# 08_-_CONNECTORS.net
KiCad netlist of a schematic drawn in Altium Designer
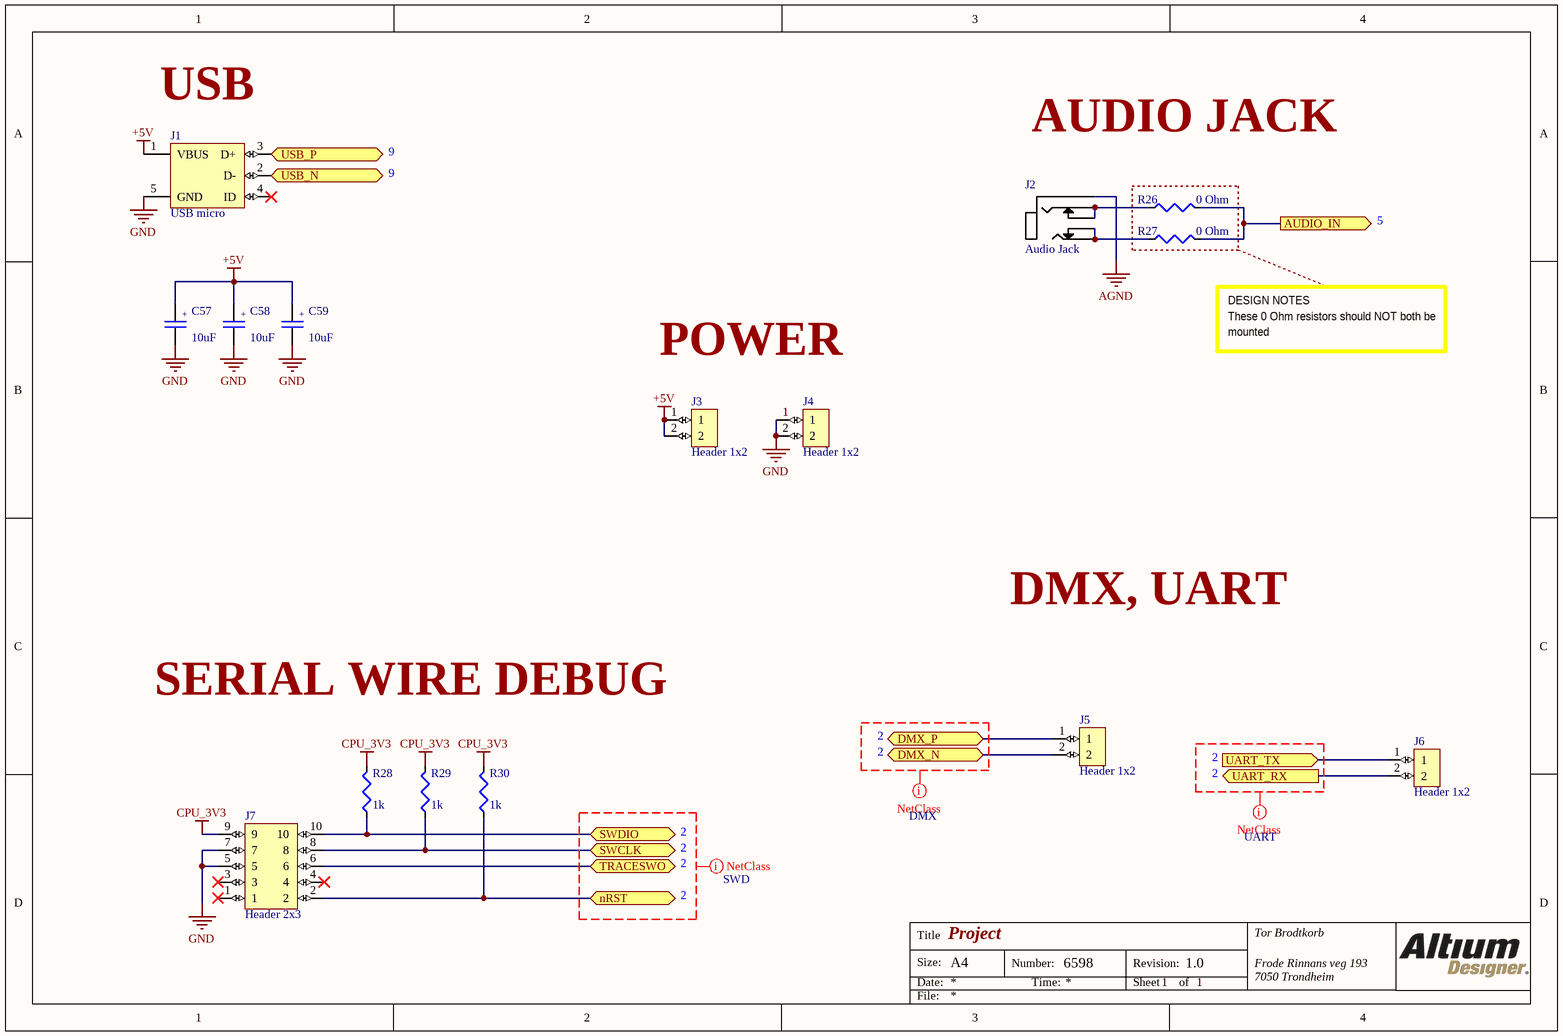
[diagram p0: [08] - CONNECTORS.SchDoc]

(export (version "E")
  (design (tool "Eeschema 10.0.6"))
  (components
    (comp (ref "C57")
      (value "10uF")
      (footprint "Capacitor electrolytic SMD 4x5.4")
      (description "El. Capacitor SMD 4x5.4")
      (fields (field (name "Comment") "EEE1HA2R2SR"))
      (libsource (lib "Passive components") (part "EEE1HA2R2SR"))
    )
    (comp (ref "C58")
      (value "10uF")
      (footprint "Capacitor electrolytic SMD 4x5.4")
      (description "El. Capacitor SMD 4x5.4")
      (fields (field (name "Comment") "EEE1HA2R2SR"))
      (libsource (lib "Passive components") (part "EEE1HA2R2SR"))
    )
    (comp (ref "C59")
      (value "10uF")
      (footprint "Capacitor electrolytic SMD 4x5.4")
      (description "El. Capacitor SMD 4x5.4")
      (fields (field (name "Comment") "EEE1HA2R2SR"))
      (libsource (lib "Passive components") (part "EEE1HA2R2SR"))
    )
    (comp (ref "J1")
      (value "USB micro")
      (footprint "USB micro")
      (libsource (lib "Connectors") (part "47590-0001"))
    )
    (comp (ref "J2")
      (value "Audio Jack")
      (footprint "Audio jack flat")
      (description "Audio jack flat 5 contacts")
      (libsource (lib "Connectors") (part "FC68133"))
    )
    (comp (ref "J3")
      (value "Header 1x2")
      (footprint "Header 1x2 2.54mm")
      (description "Header 1x2 2.54mm male")
      (libsource (lib "Connectors") (part "M20-9990246"))
    )
    (comp (ref "J4")
      (value "Header 1x2")
      (footprint "Header 1x2 2.54mm")
      (description "Header 1x2 2.54mm male")
      (libsource (lib "Connectors") (part "M20-9990246"))
    )
    (comp (ref "J5")
      (value "Header 1x2")
      (footprint "Header 1x2 2.54mm")
      (description "Header 1x2 2.54mm male")
      (libsource (lib "Connectors") (part "M20-9990246"))
    )
    (comp (ref "J6")
      (value "Header 1x2")
      (footprint "Header 1x2 2.54mm")
      (description "Header 1x2 2.54mm male")
      (libsource (lib "Connectors") (part "M20-9990246"))
    )
    (comp (ref "J7")
      (value "Header 2x3")
      (footprint "Header 2x5 1.27mm")
      (description "Header  2x5 1.27mm male")
      (libsource (lib "Connectors") (part "20021111-00010T4LF"))
    )
    (comp (ref "R26")
      (value "0 Ohm")
      (footprint "R0603")
      (description "R0603")
      (fields (field (name "Comment") "CPF-A-0603B100KE1"))
      (libsource (lib "Passive components") (part "CPF-A-0603B100KE1"))
    )
    (comp (ref "R27")
      (value "0 Ohm")
      (footprint "R0603")
      (description "R0603")
      (fields (field (name "Comment") "CPF-A-0603B100KE1"))
      (libsource (lib "Passive components") (part "CPF-A-0603B100KE1"))
    )
    (comp (ref "R28")
      (value "1k")
      (footprint "R0603")
      (description "R0603")
      (fields (field (name "Comment") "CPF-A-0603B100KE1"))
      (libsource (lib "Passive components") (part "CPF-A-0603B100KE1"))
    )
    (comp (ref "R29")
      (value "1k")
      (footprint "R0603")
      (description "R0603")
      (fields (field (name "Comment") "CPF-A-0603B100KE1"))
      (libsource (lib "Passive components") (part "CPF-A-0603B100KE1"))
    )
    (comp (ref "R30")
      (value "1k")
      (footprint "R0603")
      (description "R0603")
      (fields (field (name "Comment") "CPF-A-0603B100KE1"))
      (libsource (lib "Passive components") (part "CPF-A-0603B100KE1"))
    )
  )
  (nets
    (net (code "1") (name "+5V") (class "Default")
      (node (ref "C57") (pin "1") (pinfunction "1_1") (pintype "passive"))
      (node (ref "C58") (pin "1") (pinfunction "1_1") (pintype "passive"))
      (node (ref "C59") (pin "1") (pinfunction "1_1") (pintype "passive"))
      (node (ref "J1") (pin "1") (pinfunction "VBUS_1") (pintype "passive"))
      (node (ref "J3") (pin "1") (pinfunction "1_1") (pintype "bidirectional"))
      (node (ref "J3") (pin "2") (pinfunction "2_2") (pintype "bidirectional"))
    )
    (net (code "2") (name "/AUDIO_IN") (class "Default")
      (node (ref "R26") (pin "2") (pinfunction "2_2") (pintype "passive"))
      (node (ref "R27") (pin "2") (pinfunction "2_2") (pintype "passive"))
    )
    (net (code "3") (name "/DMX_N") (class "Default")
      (node (ref "J5") (pin "2") (pinfunction "2_2") (pintype "bidirectional"))
    )
    (net (code "4") (name "/DMX_P") (class "Default")
      (node (ref "J5") (pin "1") (pinfunction "1_1") (pintype "bidirectional"))
    )
    (net (code "5") (name "/SWCLK") (class "Default")
      (node (ref "J7") (pin "8") (pinfunction "8_8") (pintype "bidirectional"))
      (node (ref "R29") (pin "1") (pinfunction "1_1") (pintype "passive"))
    )
    (net (code "6") (name "/SWDIO") (class "Default")
      (node (ref "J7") (pin "10") (pinfunction "10_10") (pintype "bidirectional"))
      (node (ref "R28") (pin "1") (pinfunction "1_1") (pintype "passive"))
    )
    (net (code "7") (name "/TRACESWO") (class "Default")
      (node (ref "J7") (pin "6") (pinfunction "6_6") (pintype "bidirectional"))
    )
    (net (code "8") (name "/UART_RX") (class "Default")
      (node (ref "J6") (pin "2") (pinfunction "2_2") (pintype "bidirectional"))
    )
    (net (code "9") (name "/UART_TX") (class "Default")
      (node (ref "J6") (pin "1") (pinfunction "1_1") (pintype "bidirectional"))
    )
    (net (code "10") (name "/USB_N") (class "Default")
      (node (ref "J1") (pin "2") (pinfunction "D-_2") (pintype "bidirectional"))
    )
    (net (code "11") (name "/USB_P") (class "Default")
      (node (ref "J1") (pin "3") (pinfunction "D+_3") (pintype "bidirectional"))
    )
    (net (code "12") (name "/nRST") (class "Default")
      (node (ref "J7") (pin "2") (pinfunction "2_2") (pintype "bidirectional"))
      (node (ref "R30") (pin "1") (pinfunction "1_1") (pintype "passive"))
    )
    (net (code "13") (name "AGND") (class "Default")
      (node (ref "J2") (pin "1") (pinfunction "1_1") (pintype "passive"))
    )
    (net (code "14") (name "CPU_3V3") (class "Default")
      (node (ref "J7") (pin "9") (pinfunction "9_9") (pintype "bidirectional"))
      (node (ref "R28") (pin "2") (pinfunction "2_2") (pintype "passive"))
      (node (ref "R29") (pin "2") (pinfunction "2_2") (pintype "passive"))
      (node (ref "R30") (pin "2") (pinfunction "2_2") (pintype "passive"))
    )
    (net (code "15") (name "GND") (class "Default")
      (node (ref "C57") (pin "2") (pinfunction "2_2") (pintype "passive"))
      (node (ref "C58") (pin "2") (pinfunction "2_2") (pintype "passive"))
      (node (ref "C59") (pin "2") (pinfunction "2_2") (pintype "passive"))
      (node (ref "J1") (pin "5") (pinfunction "GND_5") (pintype "passive"))
      (node (ref "J4") (pin "1") (pinfunction "1_1") (pintype "bidirectional"))
      (node (ref "J4") (pin "2") (pinfunction "2_2") (pintype "bidirectional"))
      (node (ref "J7") (pin "5") (pinfunction "5_5") (pintype "bidirectional"))
      (node (ref "J7") (pin "7") (pinfunction "7_7") (pintype "bidirectional"))
    )
    (net (code "16") (name "Net-(J2-Pad2)") (class "Default")
      (node (ref "J2") (pin "2") (pinfunction "2_2") (pintype "passive"))
      (node (ref "J2") (pin "3") (pinfunction "3_3") (pintype "passive"))
      (node (ref "R26") (pin "1") (pinfunction "1_1") (pintype "passive"))
    )
    (net (code "17") (name "Net-(J2-Pad4)") (class "Default")
      (node (ref "J2") (pin "4") (pinfunction "4_4") (pintype "passive"))
      (node (ref "J2") (pin "5") (pinfunction "5_5") (pintype "passive"))
      (node (ref "R27") (pin "1") (pinfunction "1_1") (pintype "passive"))
    )
    (net (code "18") (name "unconnected-(J1-ID-Pad4)") (class "Default")
      (node (ref "J1") (pin "4") (pinfunction "ID_4") (pintype "bidirectional+no_connect"))
    )
    (net (code "19") (name "unconnected-(J7-Pad1)") (class "Default")
      (node (ref "J7") (pin "1") (pinfunction "1_1") (pintype "bidirectional+no_connect"))
    )
    (net (code "20") (name "unconnected-(J7-Pad3)") (class "Default")
      (node (ref "J7") (pin "3") (pinfunction "3_3") (pintype "bidirectional+no_connect"))
    )
    (net (code "21") (name "unconnected-(J7-Pad4)") (class "Default")
      (node (ref "J7") (pin "4") (pinfunction "4_4") (pintype "bidirectional+no_connect"))
    )
  )
)
